# I2C_Switch_I2C_EEPROM.net
KiCad netlist of a schematic drawn in Altium Designer
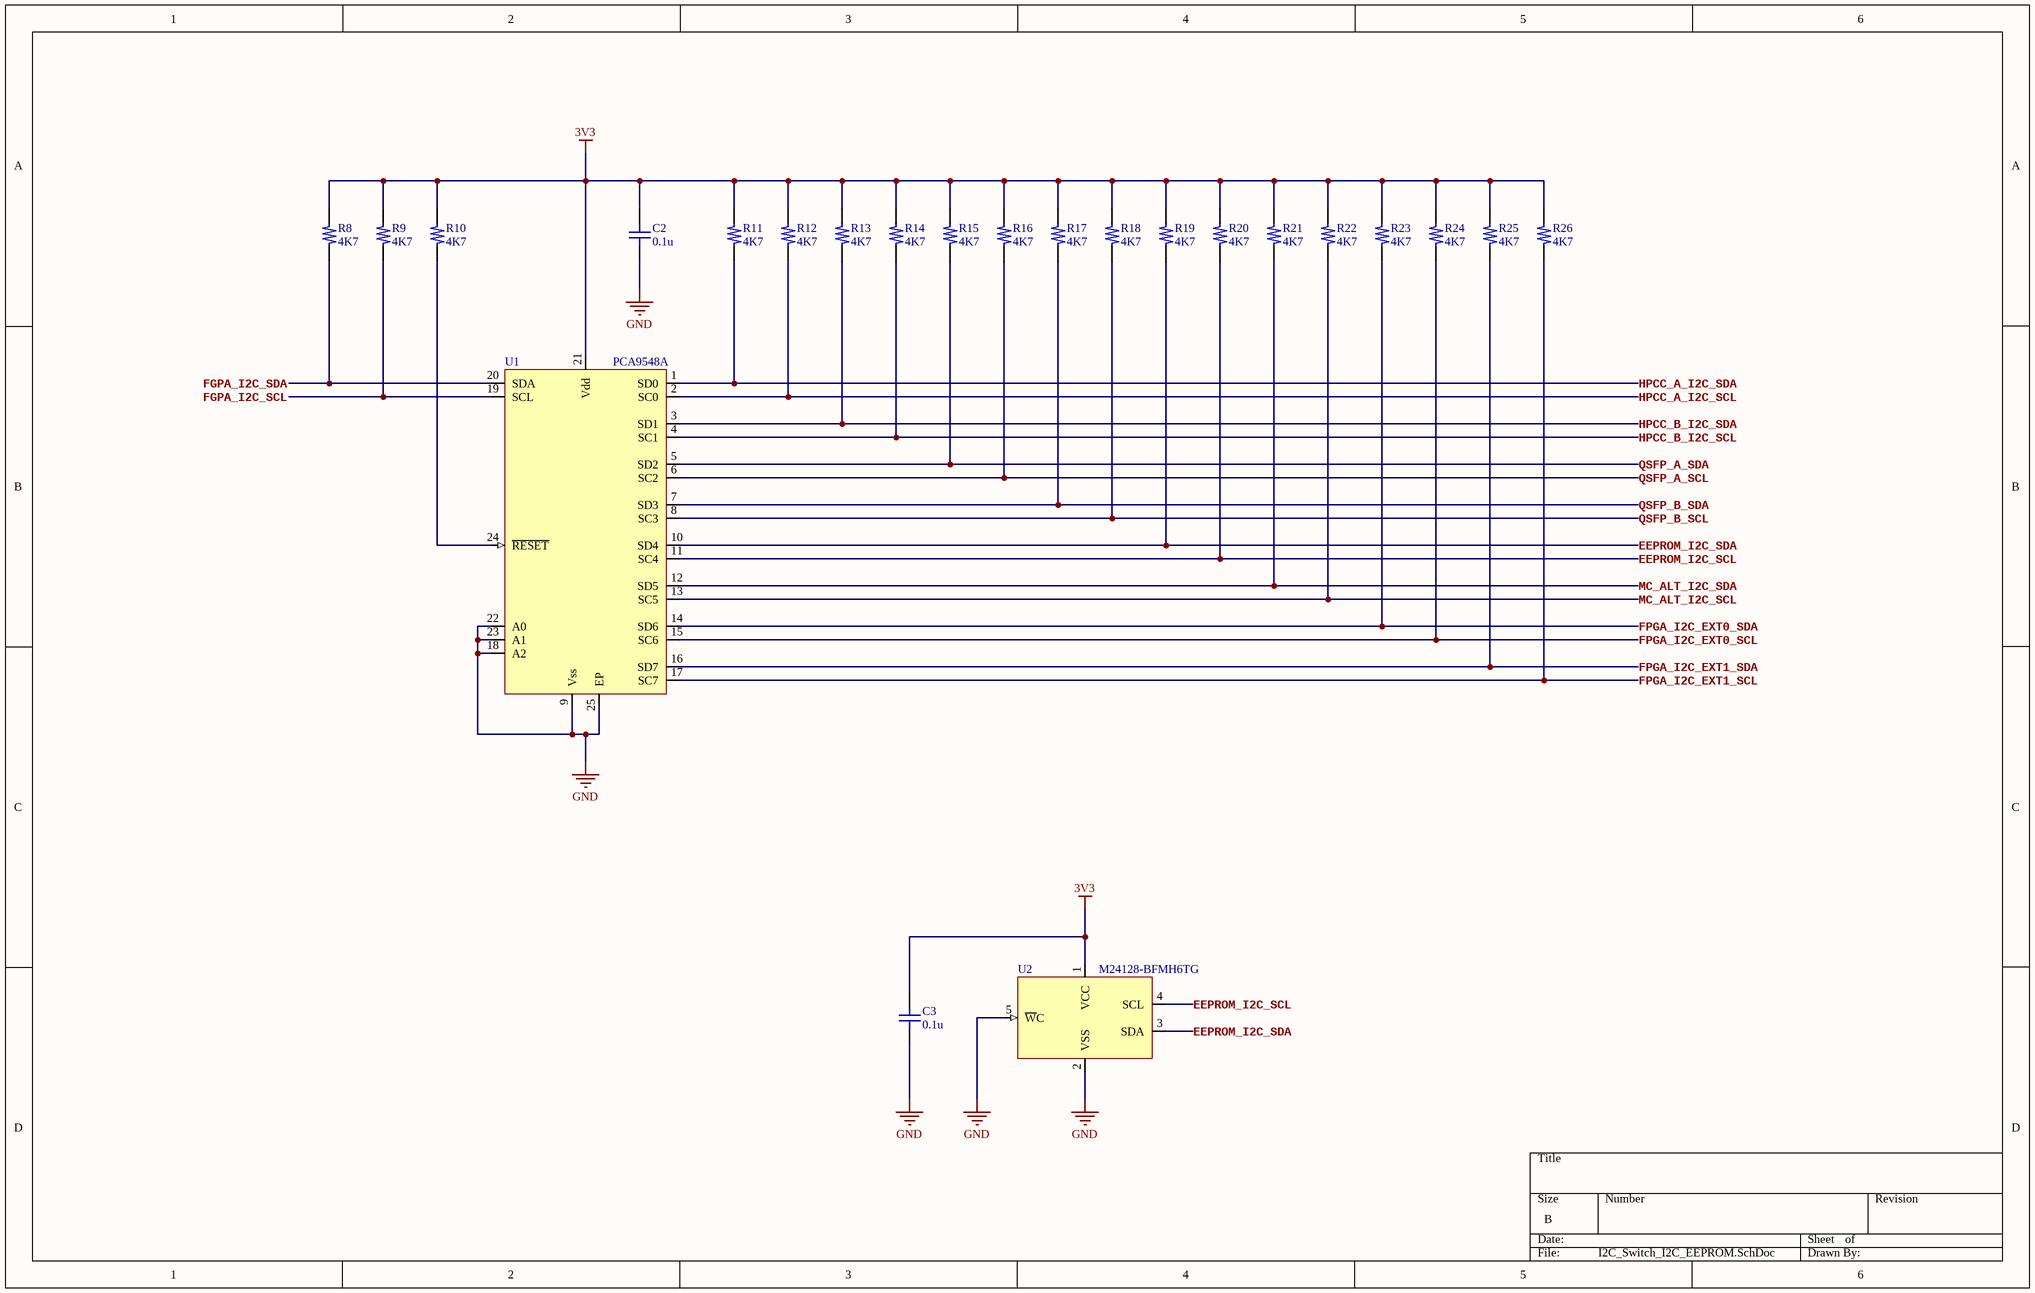
[diagram p0: I2C_Switch_I2C_EEPROM.SchDoc]

(export (version "E")
  (design (tool "Eeschema 10.0.6"))
  (components
    (comp (ref "C2")
      (value "0.1u")
      (footprint "C_0402_Generic")
      (description "0.1µF 16V X7R SMD ceramic capacitor in 0402 size")
      (fields
        (field (name "MANUFACTURER") "Murata Electronics")
        (field (name "MANUFACTURER PART NUMBER") "GRM155R71C104KA88D")
      )
      (libsource (lib "Capstone_Schematic_Library") (part "GRM155R71C104KA88D"))
    )
    (comp (ref "C3")
      (value "0.1u")
      (footprint "C_0402_Generic")
      (description "0.1µF 16V X7R SMD ceramic capacitor in 0402 size")
      (fields
        (field (name "MANUFACTURER") "Murata Electronics")
        (field (name "MANUFACTURER PART NUMBER") "GRM155R71C104KA88D")
      )
      (libsource (lib "Capstone_Schematic_Library") (part "GRM155R71C104KA88D"))
    )
    (comp (ref "R8")
      (value "4K7")
      (footprint "R_0402_Generic")
      (description "4.7KOhm 1% 1/10W SMD resistor in 0402 size")
      (fields
        (field (name "MANUFACTURER") "Panasonic")
        (field (name "MANUFACTURER PART NUMBER") "ERJ-2RKF4701X")
      )
      (libsource (lib "Capstone_Schematic_Library") (part "ERJ-2RKF4701X"))
    )
    (comp (ref "R9")
      (value "4K7")
      (footprint "R_0402_Generic")
      (description "4.7KOhm 1% 1/10W SMD resistor in 0402 size")
      (fields
        (field (name "MANUFACTURER") "Panasonic")
        (field (name "MANUFACTURER PART NUMBER") "ERJ-2RKF4701X")
      )
      (libsource (lib "Capstone_Schematic_Library") (part "ERJ-2RKF4701X"))
    )
    (comp (ref "R10")
      (value "4K7")
      (footprint "R_0402_Generic")
      (description "4.7KOhm 1% 1/10W SMD resistor in 0402 size")
      (fields
        (field (name "MANUFACTURER") "Panasonic")
        (field (name "MANUFACTURER PART NUMBER") "ERJ-2RKF4701X")
      )
      (libsource (lib "Capstone_Schematic_Library") (part "ERJ-2RKF4701X"))
    )
    (comp (ref "R11")
      (value "4K7")
      (footprint "R_0402_Generic")
      (description "4.7KOhm 1% 1/10W SMD resistor in 0402 size")
      (fields
        (field (name "MANUFACTURER") "Panasonic")
        (field (name "MANUFACTURER PART NUMBER") "ERJ-2RKF4701X")
      )
      (libsource (lib "Capstone_Schematic_Library") (part "ERJ-2RKF4701X"))
    )
    (comp (ref "R12")
      (value "4K7")
      (footprint "R_0402_Generic")
      (description "4.7KOhm 1% 1/10W SMD resistor in 0402 size")
      (fields
        (field (name "MANUFACTURER") "Panasonic")
        (field (name "MANUFACTURER PART NUMBER") "ERJ-2RKF4701X")
      )
      (libsource (lib "Capstone_Schematic_Library") (part "ERJ-2RKF4701X"))
    )
    (comp (ref "R13")
      (value "4K7")
      (footprint "R_0402_Generic")
      (description "4.7KOhm 1% 1/10W SMD resistor in 0402 size")
      (fields
        (field (name "MANUFACTURER") "Panasonic")
        (field (name "MANUFACTURER PART NUMBER") "ERJ-2RKF4701X")
      )
      (libsource (lib "Capstone_Schematic_Library") (part "ERJ-2RKF4701X"))
    )
    (comp (ref "R14")
      (value "4K7")
      (footprint "R_0402_Generic")
      (description "4.7KOhm 1% 1/10W SMD resistor in 0402 size")
      (fields
        (field (name "MANUFACTURER") "Panasonic")
        (field (name "MANUFACTURER PART NUMBER") "ERJ-2RKF4701X")
      )
      (libsource (lib "Capstone_Schematic_Library") (part "ERJ-2RKF4701X"))
    )
    (comp (ref "R15")
      (value "4K7")
      (footprint "R_0402_Generic")
      (description "4.7KOhm 1% 1/10W SMD resistor in 0402 size")
      (fields
        (field (name "MANUFACTURER") "Panasonic")
        (field (name "MANUFACTURER PART NUMBER") "ERJ-2RKF4701X")
      )
      (libsource (lib "Capstone_Schematic_Library") (part "ERJ-2RKF4701X"))
    )
    (comp (ref "R16")
      (value "4K7")
      (footprint "R_0402_Generic")
      (description "4.7KOhm 1% 1/10W SMD resistor in 0402 size")
      (fields
        (field (name "MANUFACTURER") "Panasonic")
        (field (name "MANUFACTURER PART NUMBER") "ERJ-2RKF4701X")
      )
      (libsource (lib "Capstone_Schematic_Library") (part "ERJ-2RKF4701X"))
    )
    (comp (ref "R17")
      (value "4K7")
      (footprint "R_0402_Generic")
      (description "4.7KOhm 1% 1/10W SMD resistor in 0402 size")
      (fields
        (field (name "MANUFACTURER") "Panasonic")
        (field (name "MANUFACTURER PART NUMBER") "ERJ-2RKF4701X")
      )
      (libsource (lib "Capstone_Schematic_Library") (part "ERJ-2RKF4701X"))
    )
    (comp (ref "R18")
      (value "4K7")
      (footprint "R_0402_Generic")
      (description "4.7KOhm 1% 1/10W SMD resistor in 0402 size")
      (fields
        (field (name "MANUFACTURER") "Panasonic")
        (field (name "MANUFACTURER PART NUMBER") "ERJ-2RKF4701X")
      )
      (libsource (lib "Capstone_Schematic_Library") (part "ERJ-2RKF4701X"))
    )
    (comp (ref "R19")
      (value "4K7")
      (footprint "R_0402_Generic")
      (description "4.7KOhm 1% 1/10W SMD resistor in 0402 size")
      (fields
        (field (name "MANUFACTURER") "Panasonic")
        (field (name "MANUFACTURER PART NUMBER") "ERJ-2RKF4701X")
      )
      (libsource (lib "Capstone_Schematic_Library") (part "ERJ-2RKF4701X"))
    )
    (comp (ref "R20")
      (value "4K7")
      (footprint "R_0402_Generic")
      (description "4.7KOhm 1% 1/10W SMD resistor in 0402 size")
      (fields
        (field (name "MANUFACTURER") "Panasonic")
        (field (name "MANUFACTURER PART NUMBER") "ERJ-2RKF4701X")
      )
      (libsource (lib "Capstone_Schematic_Library") (part "ERJ-2RKF4701X"))
    )
    (comp (ref "R21")
      (value "4K7")
      (footprint "R_0402_Generic")
      (description "4.7KOhm 1% 1/10W SMD resistor in 0402 size")
      (fields
        (field (name "MANUFACTURER") "Panasonic")
        (field (name "MANUFACTURER PART NUMBER") "ERJ-2RKF4701X")
      )
      (libsource (lib "Capstone_Schematic_Library") (part "ERJ-2RKF4701X"))
    )
    (comp (ref "R22")
      (value "4K7")
      (footprint "R_0402_Generic")
      (description "4.7KOhm 1% 1/10W SMD resistor in 0402 size")
      (fields
        (field (name "MANUFACTURER") "Panasonic")
        (field (name "MANUFACTURER PART NUMBER") "ERJ-2RKF4701X")
      )
      (libsource (lib "Capstone_Schematic_Library") (part "ERJ-2RKF4701X"))
    )
    (comp (ref "R23")
      (value "4K7")
      (footprint "R_0402_Generic")
      (description "4.7KOhm 1% 1/10W SMD resistor in 0402 size")
      (fields
        (field (name "MANUFACTURER") "Panasonic")
        (field (name "MANUFACTURER PART NUMBER") "ERJ-2RKF4701X")
      )
      (libsource (lib "Capstone_Schematic_Library") (part "ERJ-2RKF4701X"))
    )
    (comp (ref "R24")
      (value "4K7")
      (footprint "R_0402_Generic")
      (description "4.7KOhm 1% 1/10W SMD resistor in 0402 size")
      (fields
        (field (name "MANUFACTURER") "Panasonic")
        (field (name "MANUFACTURER PART NUMBER") "ERJ-2RKF4701X")
      )
      (libsource (lib "Capstone_Schematic_Library") (part "ERJ-2RKF4701X"))
    )
    (comp (ref "R25")
      (value "4K7")
      (footprint "R_0402_Generic")
      (description "4.7KOhm 1% 1/10W SMD resistor in 0402 size")
      (fields
        (field (name "MANUFACTURER") "Panasonic")
        (field (name "MANUFACTURER PART NUMBER") "ERJ-2RKF4701X")
      )
      (libsource (lib "Capstone_Schematic_Library") (part "ERJ-2RKF4701X"))
    )
    (comp (ref "R26")
      (value "4K7")
      (footprint "R_0402_Generic")
      (description "4.7KOhm 1% 1/10W SMD resistor in 0402 size")
      (fields
        (field (name "MANUFACTURER") "Panasonic")
        (field (name "MANUFACTURER PART NUMBER") "ERJ-2RKF4701X")
      )
      (libsource (lib "Capstone_Schematic_Library") (part "ERJ-2RKF4701X"))
    )
    (comp (ref "U1")
      (value "PCA9548A")
      (footprint "HVQFN24_NXP")
      (description "8-channel I 2 C-bus switch, 24-HVQFN")
      (fields (field (name "MANUFACTURER") "NXP") (field (name "MANUFACTURER PART NUMBER") "PCA9548ABS,118"))
      (libsource (lib "Capstone_Schematic_Library") (part "PCA9548ABS,118"))
    )
    (comp (ref "U2")
      (value "M24128-BFMH6TG")
      (footprint "STM_DFN5")
      (description "EEPROM 128Kbit I2C 1MHz 450 ns")
      (fields (field (name "MANUFACTURER") "STMicroelectronics"))
      (libsource (lib "Capstone_Schematic_Library") (part "M24128-BFMH6TG"))
    )
  )
  (nets
    (net (code "1") (name "/EEPROM_I2C_SCL") (class "Default")
      (node (ref "R20") (pin "1") (pinfunction "1_1") (pintype "passive"))
      (node (ref "U1") (pin "11") (pinfunction "SC4_11") (pintype "bidirectional"))
      (node (ref "U2") (pin "4") (pinfunction "SCL_4") (pintype "bidirectional"))
    )
    (net (code "2") (name "/EEPROM_I2C_SDA") (class "Default")
      (node (ref "R19") (pin "1") (pinfunction "1_1") (pintype "passive"))
      (node (ref "U1") (pin "10") (pinfunction "SD4_10") (pintype "bidirectional"))
      (node (ref "U2") (pin "3") (pinfunction "SDA_3") (pintype "bidirectional"))
    )
    (net (code "3") (name "/FGPA_I2C_SCL") (class "Default")
      (node (ref "R9") (pin "1") (pinfunction "1_1") (pintype "passive"))
      (node (ref "U1") (pin "19") (pinfunction "SCL_19") (pintype "bidirectional"))
    )
    (net (code "4") (name "/FGPA_I2C_SDA") (class "Default")
      (node (ref "R8") (pin "1") (pinfunction "1_1") (pintype "passive"))
      (node (ref "U1") (pin "20") (pinfunction "SDA_20") (pintype "bidirectional"))
    )
    (net (code "5") (name "/FPGA_I2C_EXT0_SCL") (class "Default")
      (node (ref "R24") (pin "1") (pinfunction "1_1") (pintype "passive"))
      (node (ref "U1") (pin "15") (pinfunction "SC6_15") (pintype "bidirectional"))
    )
    (net (code "6") (name "/FPGA_I2C_EXT0_SDA") (class "Default")
      (node (ref "R23") (pin "1") (pinfunction "1_1") (pintype "passive"))
      (node (ref "U1") (pin "14") (pinfunction "SD6_14") (pintype "bidirectional"))
    )
    (net (code "7") (name "/FPGA_I2C_EXT1_SCL") (class "Default")
      (node (ref "R26") (pin "1") (pinfunction "1_1") (pintype "passive"))
      (node (ref "U1") (pin "17") (pinfunction "SC7_17") (pintype "bidirectional"))
    )
    (net (code "8") (name "/FPGA_I2C_EXT1_SDA") (class "Default")
      (node (ref "R25") (pin "1") (pinfunction "1_1") (pintype "passive"))
      (node (ref "U1") (pin "16") (pinfunction "SD7_16") (pintype "bidirectional"))
    )
    (net (code "9") (name "/HPCC_A_I2C_SCL") (class "Default")
      (node (ref "R12") (pin "1") (pinfunction "1_1") (pintype "passive"))
      (node (ref "U1") (pin "2") (pinfunction "SC0_2") (pintype "bidirectional"))
    )
    (net (code "10") (name "/HPCC_A_I2C_SDA") (class "Default")
      (node (ref "R11") (pin "1") (pinfunction "1_1") (pintype "passive"))
      (node (ref "U1") (pin "1") (pinfunction "SD0_1") (pintype "bidirectional"))
    )
    (net (code "11") (name "/HPCC_B_I2C_SCL") (class "Default")
      (node (ref "R14") (pin "1") (pinfunction "1_1") (pintype "passive"))
      (node (ref "U1") (pin "4") (pinfunction "SC1_4") (pintype "bidirectional"))
    )
    (net (code "12") (name "/HPCC_B_I2C_SDA") (class "Default")
      (node (ref "R13") (pin "1") (pinfunction "1_1") (pintype "passive"))
      (node (ref "U1") (pin "3") (pinfunction "SD1_3") (pintype "bidirectional"))
    )
    (net (code "13") (name "/MC_ALT_I2C_SCL") (class "Default")
      (node (ref "R22") (pin "1") (pinfunction "1_1") (pintype "passive"))
      (node (ref "U1") (pin "13") (pinfunction "SC5_13") (pintype "bidirectional"))
    )
    (net (code "14") (name "/MC_ALT_I2C_SDA") (class "Default")
      (node (ref "R21") (pin "1") (pinfunction "1_1") (pintype "passive"))
      (node (ref "U1") (pin "12") (pinfunction "SD5_12") (pintype "bidirectional"))
    )
    (net (code "15") (name "/QSFP_A_SCL") (class "Default")
      (node (ref "R16") (pin "1") (pinfunction "1_1") (pintype "passive"))
      (node (ref "U1") (pin "6") (pinfunction "SC2_6") (pintype "bidirectional"))
    )
    (net (code "16") (name "/QSFP_A_SDA") (class "Default")
      (node (ref "R15") (pin "1") (pinfunction "1_1") (pintype "passive"))
      (node (ref "U1") (pin "5") (pinfunction "SD2_5") (pintype "bidirectional"))
    )
    (net (code "17") (name "/QSFP_B_SCL") (class "Default")
      (node (ref "R18") (pin "1") (pinfunction "1_1") (pintype "passive"))
      (node (ref "U1") (pin "8") (pinfunction "SC3_8") (pintype "bidirectional"))
    )
    (net (code "18") (name "/QSFP_B_SDA") (class "Default")
      (node (ref "R17") (pin "1") (pinfunction "1_1") (pintype "passive"))
      (node (ref "U1") (pin "7") (pinfunction "SD3_7") (pintype "bidirectional"))
    )
    (net (code "19") (name "3V3") (class "Default")
      (node (ref "C2") (pin "2") (pinfunction "2_2") (pintype "passive"))
      (node (ref "C3") (pin "2") (pinfunction "2_2") (pintype "passive"))
      (node (ref "R10") (pin "2") (pinfunction "2_2") (pintype "passive"))
      (node (ref "R11") (pin "2") (pinfunction "2_2") (pintype "passive"))
      (node (ref "R12") (pin "2") (pinfunction "2_2") (pintype "passive"))
      (node (ref "R13") (pin "2") (pinfunction "2_2") (pintype "passive"))
      (node (ref "R14") (pin "2") (pinfunction "2_2") (pintype "passive"))
      (node (ref "R15") (pin "2") (pinfunction "2_2") (pintype "passive"))
      (node (ref "R16") (pin "2") (pinfunction "2_2") (pintype "passive"))
      (node (ref "R17") (pin "2") (pinfunction "2_2") (pintype "passive"))
      (node (ref "R18") (pin "2") (pinfunction "2_2") (pintype "passive"))
      (node (ref "R19") (pin "2") (pinfunction "2_2") (pintype "passive"))
      (node (ref "R20") (pin "2") (pinfunction "2_2") (pintype "passive"))
      (node (ref "R21") (pin "2") (pinfunction "2_2") (pintype "passive"))
      (node (ref "R22") (pin "2") (pinfunction "2_2") (pintype "passive"))
      (node (ref "R23") (pin "2") (pinfunction "2_2") (pintype "passive"))
      (node (ref "R24") (pin "2") (pinfunction "2_2") (pintype "passive"))
      (node (ref "R25") (pin "2") (pinfunction "2_2") (pintype "passive"))
      (node (ref "R26") (pin "2") (pinfunction "2_2") (pintype "passive"))
      (node (ref "R8") (pin "2") (pinfunction "2_2") (pintype "passive"))
      (node (ref "R9") (pin "2") (pinfunction "2_2") (pintype "passive"))
      (node (ref "U1") (pin "21") (pinfunction "Vdd_21") (pintype "power_in"))
      (node (ref "U2") (pin "1") (pinfunction "VCC_1") (pintype "power_in"))
    )
    (net (code "20") (name "GND") (class "Default")
      (node (ref "C2") (pin "1") (pinfunction "1_1") (pintype "passive"))
      (node (ref "C3") (pin "1") (pinfunction "1_1") (pintype "passive"))
      (node (ref "U1") (pin "18") (pinfunction "A2_18") (pintype "passive"))
      (node (ref "U1") (pin "22") (pinfunction "A0_22") (pintype "passive"))
      (node (ref "U1") (pin "23") (pinfunction "A1_23") (pintype "passive"))
      (node (ref "U1") (pin "25") (pinfunction "EP_25") (pintype "power_in"))
      (node (ref "U1") (pin "9") (pinfunction "Vss_9") (pintype "power_in"))
      (node (ref "U2") (pin "2") (pinfunction "VSS_2") (pintype "power_in"))
      (node (ref "U2") (pin "5") (pinfunction "~{W}C_5") (pintype "input"))
    )
    (net (code "21") (name "Net-(U1-~{RESET})") (class "Default")
      (node (ref "R10") (pin "1") (pinfunction "1_1") (pintype "passive"))
      (node (ref "U1") (pin "24") (pinfunction "~{RESET}_24") (pintype "input"))
    )
  )
)
